# cs301_Group_12.net
KiCad netlist of a schematic drawn in Altium Designer
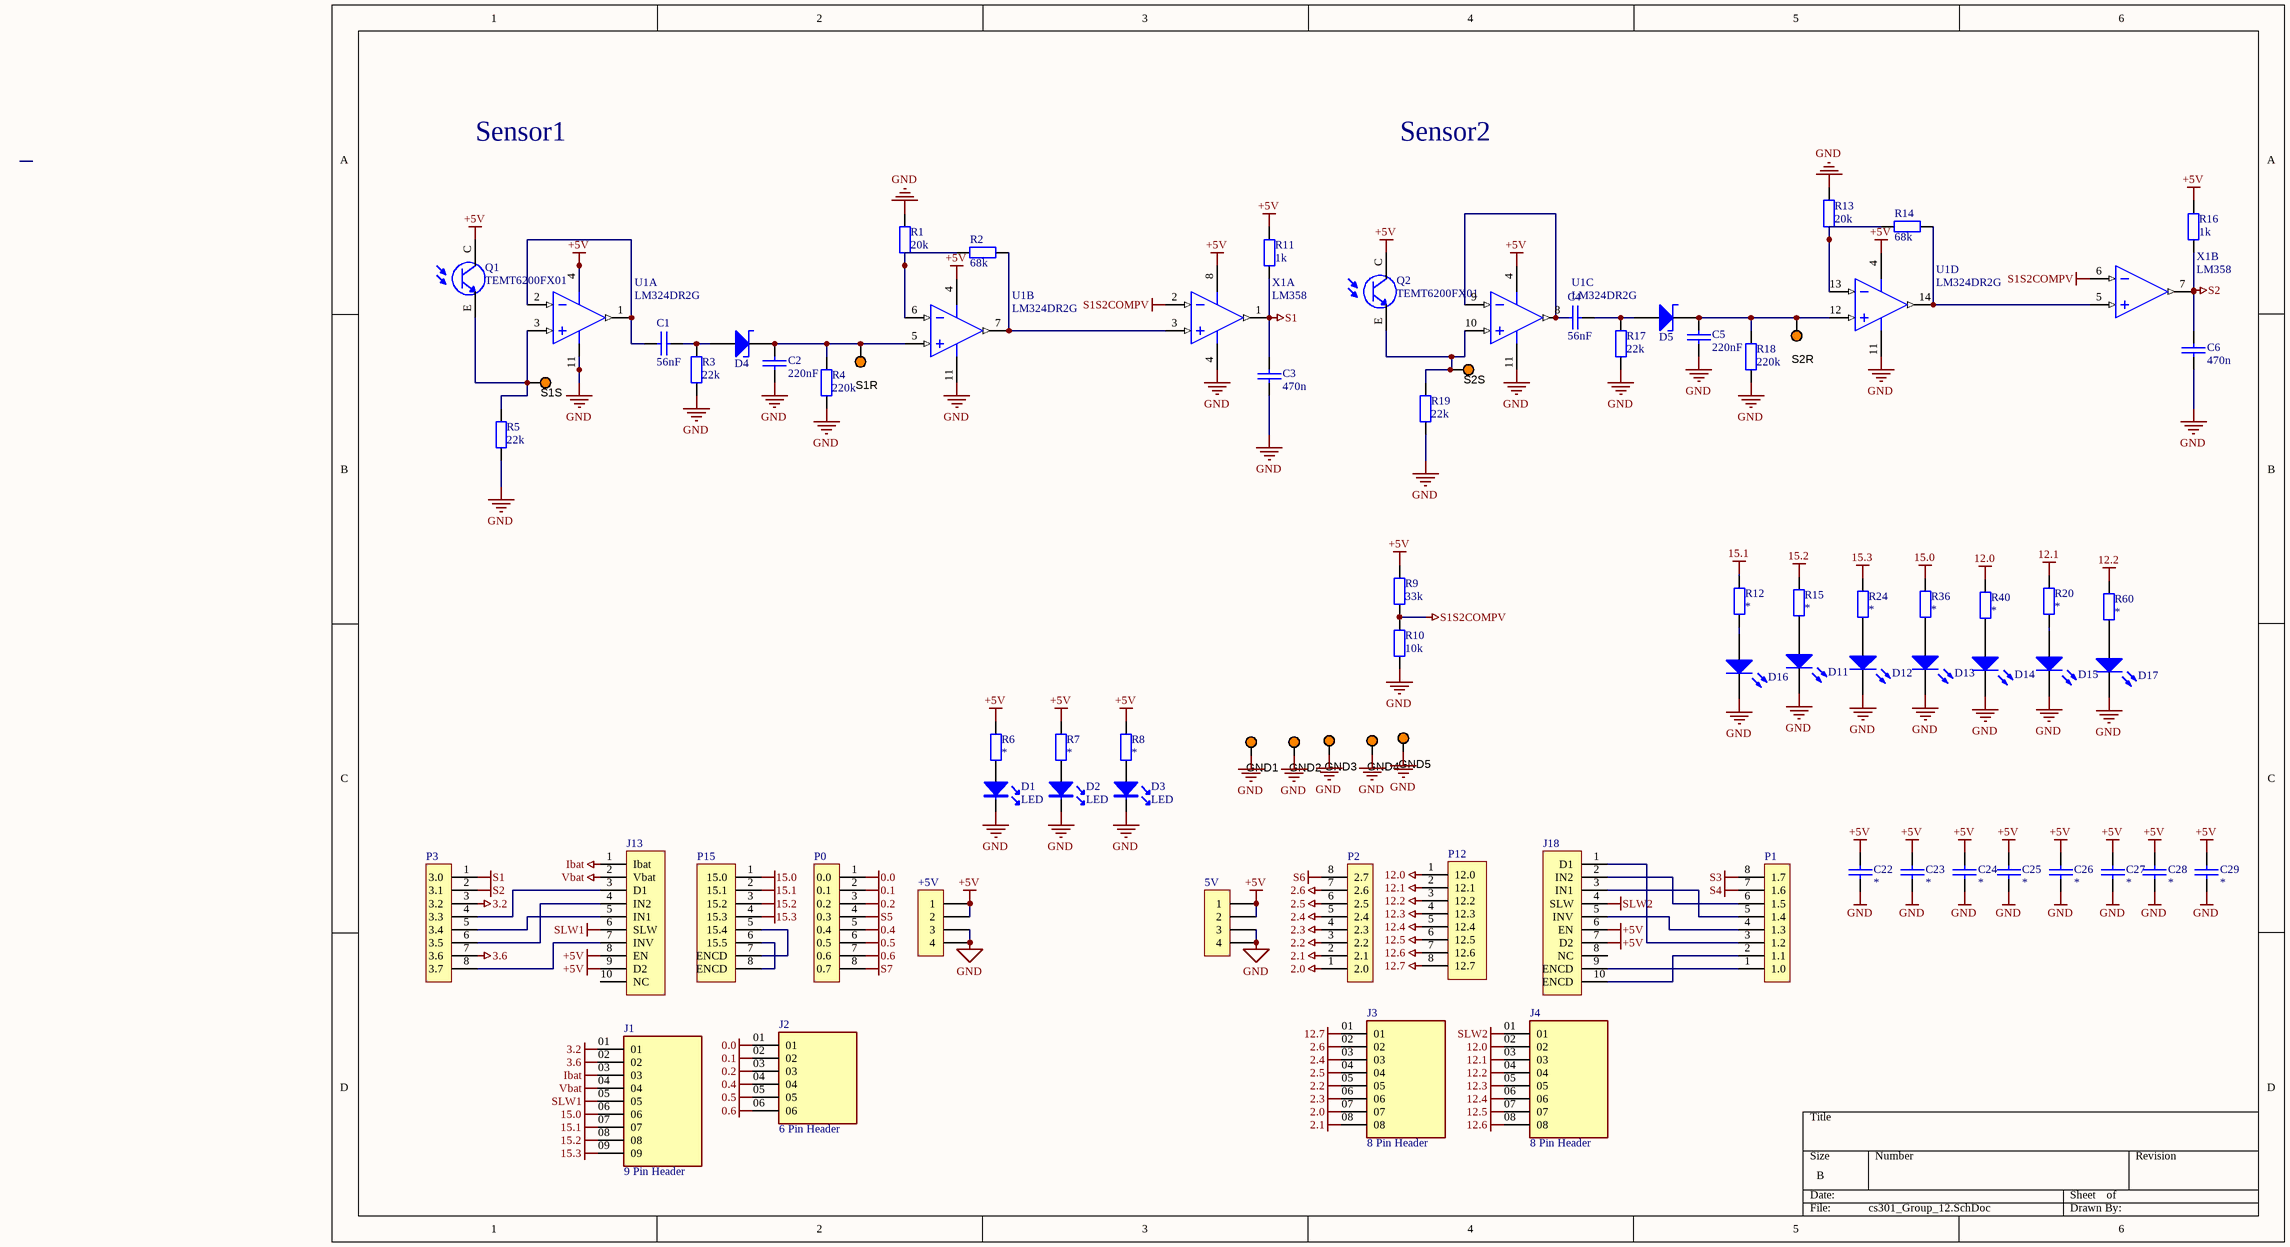
[diagram p0: cs301_Group_12.SchDoc]

(export (version "E")
  (design (tool "Eeschema 10.0.6"))
  (components
    (comp (ref "+5V")
      (value "5V")
      (footprint "IDC4")
      (description "Connector")
      (libsource (lib "Miscellaneous Devices") (part "CON4"))
    )
    (comp (ref "5V")
      (value "5V")
      (footprint "IDC4")
      (description "Connector")
      (libsource (lib "Miscellaneous Devices") (part "CON4"))
    )
    (comp (ref "C1")
      (value "56nF")
      (footprint "0805 CAP")
      (description "SMT ceramic capacitor 0805 size")
      (libsource (lib "EE209_Library") (part "CerCap_SMT_0805"))
    )
    (comp (ref "C2")
      (value "220nF")
      (footprint "0805 CAP")
      (description "SMT ceramic capacitor 0805 size")
      (libsource (lib "EE209_Library") (part "CerCap_SMT_0805"))
    )
    (comp (ref "C3")
      (value "470n")
      (footprint "0805 CAP")
      (description "SMT ceramic capacitor 0805 size")
      (libsource (lib "EE209_Library") (part "CerCap_SMT_0805"))
    )
    (comp (ref "C4")
      (value "56nF")
      (footprint "0805 CAP")
      (description "SMT ceramic capacitor 0805 size")
      (libsource (lib "EE209_Library") (part "CerCap_SMT_0805"))
    )
    (comp (ref "C5")
      (value "220nF")
      (footprint "0805 CAP")
      (description "SMT ceramic capacitor 0805 size")
      (libsource (lib "EE209_Library") (part "CerCap_SMT_0805"))
    )
    (comp (ref "C6")
      (value "470n")
      (footprint "0805 CAP")
      (description "SMT ceramic capacitor 0805 size")
      (libsource (lib "EE209_Library") (part "CerCap_SMT_0805"))
    )
    (comp (ref "C22")
      (value "*")
      (footprint "0805 CAP")
      (description "SMT ceramic capacitor 0805 size")
      (libsource (lib "EE209_Library") (part "CerCap_SMT_0805"))
    )
    (comp (ref "C23")
      (value "*")
      (footprint "0805 CAP")
      (description "SMT ceramic capacitor 0805 size")
      (libsource (lib "EE209_Library") (part "CerCap_SMT_0805"))
    )
    (comp (ref "C24")
      (value "*")
      (footprint "0805 CAP")
      (description "SMT ceramic capacitor 0805 size")
      (libsource (lib "EE209_Library") (part "CerCap_SMT_0805"))
    )
    (comp (ref "C25")
      (value "*")
      (footprint "0805 CAP")
      (description "SMT ceramic capacitor 0805 size")
      (libsource (lib "EE209_Library") (part "CerCap_SMT_0805"))
    )
    (comp (ref "C26")
      (value "*")
      (footprint "0805 CAP")
      (description "SMT ceramic capacitor 0805 size")
      (libsource (lib "EE209_Library") (part "CerCap_SMT_0805"))
    )
    (comp (ref "C27")
      (value "*")
      (footprint "0805 CAP")
      (description "SMT ceramic capacitor 0805 size")
      (libsource (lib "EE209_Library") (part "CerCap_SMT_0805"))
    )
    (comp (ref "C28")
      (value "*")
      (footprint "0805 CAP")
      (description "SMT ceramic capacitor 0805 size")
      (libsource (lib "EE209_Library") (part "CerCap_SMT_0805"))
    )
    (comp (ref "C29")
      (value "*")
      (footprint "0805 CAP")
      (description "SMT ceramic capacitor 0805 size")
      (libsource (lib "EE209_Library") (part "CerCap_SMT_0805"))
    )
    (comp (ref "D1") (value "LED") (footprint "LED0.1/5MM") (libsource (lib "COMSYS301_2013") (part "LED")))
    (comp (ref "D2") (value "LED") (footprint "LED0.1/5MM") (libsource (lib "COMSYS301_2013") (part "LED")))
    (comp (ref "D3") (value "LED") (footprint "LED0.1/5MM") (libsource (lib "COMSYS301_2013") (part "LED")))
    (comp (ref "D4")
      (value "BZT52H-B4V7")
      (footprint "SOD123")
      (description "SMT zener diode with SOD123 package")
      (fields
        (field (name "MANUFACTURER") "Nexperia USA Inc.")
        (field (name "MANUFACTURER PART NUMBER") "BZT52H-B4V7,115")
      )
      (libsource (lib "EE209_Library") (part "Zener_SMT_SOD123"))
    )
    (comp (ref "D5")
      (value "BZT52H-B4V7")
      (footprint "SOD123")
      (description "SMT zener diode with SOD123 package")
      (fields
        (field (name "MANUFACTURER") "Nexperia USA Inc.")
        (field (name "MANUFACTURER PART NUMBER") "BZT52H-B4V7,115")
      )
      (libsource (lib "EE209_Library") (part "Zener_SMT_SOD123"))
    )
    (comp (ref "D11")
      (value "LTST-C170KGKT")
      (footprint "0805 LED")
      (description "SMT LED 0805 size")
      (fields (field (name "MANUFACTURER") "Lite-On Inc."))
      (libsource (lib "EE209_Library") (part "LED_SMT_0805"))
    )
    (comp (ref "D12")
      (value "LTST-C170KGKT")
      (footprint "0805 LED")
      (description "SMT LED 0805 size")
      (fields (field (name "MANUFACTURER") "Lite-On Inc."))
      (libsource (lib "EE209_Library") (part "LED_SMT_0805"))
    )
    (comp (ref "D13")
      (value "LTST-C170KGKT")
      (footprint "0805 LED")
      (description "SMT LED 0805 size")
      (fields (field (name "MANUFACTURER") "Lite-On Inc."))
      (libsource (lib "EE209_Library") (part "LED_SMT_0805"))
    )
    (comp (ref "D14")
      (value "LTST-C170KGKT")
      (footprint "0805 LED")
      (description "SMT LED 0805 size")
      (fields (field (name "MANUFACTURER") "Lite-On Inc."))
      (libsource (lib "EE209_Library") (part "LED_SMT_0805"))
    )
    (comp (ref "D15")
      (value "LTST-C170KGKT")
      (footprint "0805 LED")
      (description "SMT LED 0805 size")
      (fields (field (name "MANUFACTURER") "Lite-On Inc."))
      (libsource (lib "EE209_Library") (part "LED_SMT_0805"))
    )
    (comp (ref "D16")
      (value "LTST-C170KGKT")
      (footprint "0805 LED")
      (description "SMT LED 0805 size")
      (fields (field (name "MANUFACTURER") "Lite-On Inc."))
      (libsource (lib "EE209_Library") (part "LED_SMT_0805"))
    )
    (comp (ref "D17")
      (value "LTST-C170KGKT")
      (footprint "0805 LED")
      (description "SMT LED 0805 size")
      (fields (field (name "MANUFACTURER") "Lite-On Inc."))
      (libsource (lib "EE209_Library") (part "LED_SMT_0805"))
    )
    (comp (ref "GND1")
      (value "5003")
      (footprint "TP_TH")
      (description "Test Point, Orange, 1-Pin THD, RoHS")
      (libsource (lib "EE209_Library") (part "TestPoint"))
    )
    (comp (ref "GND2")
      (value "5003")
      (footprint "TP_TH")
      (description "Test Point, Orange, 1-Pin THD, RoHS")
      (libsource (lib "EE209_Library") (part "TestPoint"))
    )
    (comp (ref "GND3")
      (value "5003")
      (footprint "TP_TH")
      (description "Test Point, Orange, 1-Pin THD, RoHS")
      (libsource (lib "EE209_Library") (part "TestPoint"))
    )
    (comp (ref "GND4")
      (value "5003")
      (footprint "TP_TH")
      (description "Test Point, Orange, 1-Pin THD, RoHS")
      (libsource (lib "EE209_Library") (part "TestPoint"))
    )
    (comp (ref "GND5")
      (value "5003")
      (footprint "TP_TH")
      (description "Test Point, Orange, 1-Pin THD, RoHS")
      (libsource (lib "EE209_Library") (part "TestPoint"))
    )
    (comp (ref "J1")
      (value "9 Pin Header")
      (footprint "SAMTEC_MTSW-109-22-G-S-440")
      (fields (field (name "MP") "MTSW-109-22-G-S-440"))
      (libsource (lib "MTSW-109-22-G-S-440") (part "MTSW-109-22-G-S-440"))
    )
    (comp (ref "J2")
      (value "6 Pin Header")
      (footprint "SAMTEC_TSW-106-07-H-S")
      (description "Connector Header Through Hole 6 position 0.100 (2.54mm)")
      (fields (field (name "MP") "TSW-106-07-H-S") (field (name "MF") "Samtec"))
      (libsource (lib "TSW-106-07-H-S") (part "TSW-106-07-H-S"))
    )
    (comp (ref "J3")
      (value "8 Pin Header")
      (footprint "SAMTEC_TSW-108-05-F-S")
      (fields (field (name "MP") "TSW-108-05-F-S"))
      (libsource (lib "TSW-108-05-F-S") (part "TSW-108-05-F-S"))
    )
    (comp (ref "J4")
      (value "8 Pin Header")
      (footprint "SAMTEC_TSW-108-05-F-S")
      (fields (field (name "MP") "TSW-108-05-F-S"))
      (libsource (lib "TSW-108-05-F-S") (part "TSW-108-05-F-S"))
    )
    (comp (ref "J13")
      (value "CON10")
      (footprint "idc10")
      (description "Connector")
      (libsource (lib "") (part "CON10_1"))
    )
    (comp (ref "J18")
      (value "CON10")
      (footprint "IDC10")
      (description "Connector")
      (libsource (lib "Miscellaneous Devices") (part "CON10"))
    )
    (comp (ref "P0")
      (value "P0")
      (footprint "idc8")
      (description "Connector")
      (libsource (lib "Miscellaneous Devices") (part "CON8"))
    )
    (comp (ref "P1")
      (value "P1")
      (footprint "idc8")
      (description "Connector")
      (libsource (lib "") (part "CON8_1"))
    )
    (comp (ref "P2")
      (value "P2")
      (footprint "idc8")
      (description "Connector")
      (libsource (lib "") (part "CON8_2"))
    )
    (comp (ref "P3")
      (value "P3")
      (footprint "idc8")
      (description "Connector")
      (libsource (lib "Miscellaneous Devices") (part "CON8"))
    )
    (comp (ref "P12")
      (value "P12")
      (footprint "idc8")
      (description "Connector")
      (libsource (lib "Miscellaneous Devices") (part "CON8_1"))
    )
    (comp (ref "P15")
      (value "P15")
      (footprint "idc8")
      (description "Connector")
      (libsource (lib "") (part "CON8_1_1"))
    )
    (comp (ref "Q1")
      (value "TEMT6200FX01")
      (footprint "XDCR_TEMT6200FX01")
      (description "Phototransistors 550nm Top View 0805 (2012 Metric)")
      (fields (field (name "MF") "Vishay Semiconductor"))
      (libsource (lib "TEMT6200FX01") (part "TEMT6200FX01"))
    )
    (comp (ref "Q2")
      (value "TEMT6200FX01")
      (footprint "XDCR_TEMT6200FX01")
      (description "Phototransistors 550nm Top View 0805 (2012 Metric)")
      (fields (field (name "MF") "Vishay Semiconductor"))
      (libsource (lib "TEMT6200FX01") (part "TEMT6200FX01"))
    )
    (comp (ref "R1")
      (value "20k")
      (footprint "0805 RES")
      (description "0805 resistor")
      (fields (field (name "PUBLISHER") "Altium Limited"))
      (libsource (lib "EE209_Library") (part "Res_SMT_0805"))
    )
    (comp (ref "R2")
      (value "68k")
      (footprint "0805 RES")
      (description "0805 resistor")
      (fields (field (name "PUBLISHER") "Altium Limited"))
      (libsource (lib "") (part "Res_SMT_0805_2"))
    )
    (comp (ref "R3")
      (value "22k")
      (footprint "0805 RES")
      (description "0805 resistor")
      (fields (field (name "PUBLISHER") "Altium Limited"))
      (libsource (lib "EE209_Library") (part "Res_SMT_0805"))
    )
    (comp (ref "R4")
      (value "220k")
      (footprint "0805 RES")
      (description "0805 resistor")
      (fields (field (name "PUBLISHER") "Altium Limited"))
      (libsource (lib "EE209_Library") (part "Res_SMT_0805"))
    )
    (comp (ref "R5")
      (value "22k")
      (footprint "0805 RES")
      (description "0805 resistor")
      (fields (field (name "PUBLISHER") "Altium Limited"))
      (libsource (lib "EE209_Library") (part "Res_SMT_0805"))
    )
    (comp (ref "R6")
      (value "*")
      (footprint "0805 RES")
      (description "0805 resistor")
      (fields (field (name "PUBLISHER") "Altium Limited"))
      (libsource (lib "EE209_Library") (part "Res_SMT_0805"))
    )
    (comp (ref "R7")
      (value "*")
      (footprint "0805 RES")
      (description "0805 resistor")
      (fields (field (name "PUBLISHER") "Altium Limited"))
      (libsource (lib "EE209_Library") (part "Res_SMT_0805"))
    )
    (comp (ref "R8")
      (value "*")
      (footprint "0805 RES")
      (description "0805 resistor")
      (fields (field (name "PUBLISHER") "Altium Limited"))
      (libsource (lib "EE209_Library") (part "Res_SMT_0805"))
    )
    (comp (ref "R9")
      (value "33k")
      (footprint "0805 RES")
      (description "0805 resistor")
      (fields (field (name "PUBLISHER") "Altium Limited"))
      (libsource (lib "") (part "Res_SMT_0805_1"))
    )
    (comp (ref "R10")
      (value "10k")
      (footprint "0805 RES")
      (description "0805 resistor")
      (fields (field (name "PUBLISHER") "Altium Limited"))
      (libsource (lib "") (part "Res_SMT_0805_1"))
    )
    (comp (ref "R11")
      (value "1k")
      (footprint "0805 RES")
      (description "0805 resistor")
      (fields (field (name "PUBLISHER") "Altium Limited"))
      (libsource (lib "") (part "Res_SMT_0805_1"))
    )
    (comp (ref "R12")
      (value "*")
      (footprint "0805 RES")
      (description "0805 resistor")
      (fields (field (name "PUBLISHER") "Altium Limited"))
      (libsource (lib "EE209_Library") (part "Res_SMT_0805"))
    )
    (comp (ref "R13")
      (value "20k")
      (footprint "0805 RES")
      (description "0805 resistor")
      (fields (field (name "PUBLISHER") "Altium Limited"))
      (libsource (lib "EE209_Library") (part "Res_SMT_0805"))
    )
    (comp (ref "R14")
      (value "68k")
      (footprint "0805 RES")
      (description "0805 resistor")
      (fields (field (name "PUBLISHER") "Altium Limited"))
      (libsource (lib "") (part "Res_SMT_0805_2"))
    )
    (comp (ref "R15")
      (value "*")
      (footprint "0805 RES")
      (description "0805 resistor")
      (fields (field (name "PUBLISHER") "Altium Limited"))
      (libsource (lib "EE209_Library") (part "Res_SMT_0805"))
    )
    (comp (ref "R16")
      (value "1k")
      (footprint "0805 RES")
      (description "0805 resistor")
      (fields (field (name "PUBLISHER") "Altium Limited"))
      (libsource (lib "") (part "Res_SMT_0805_1"))
    )
    (comp (ref "R17")
      (value "22k")
      (footprint "0805 RES")
      (description "0805 resistor")
      (fields (field (name "PUBLISHER") "Altium Limited"))
      (libsource (lib "EE209_Library") (part "Res_SMT_0805"))
    )
    (comp (ref "R18")
      (value "220k")
      (footprint "0805 RES")
      (description "0805 resistor")
      (fields (field (name "PUBLISHER") "Altium Limited"))
      (libsource (lib "EE209_Library") (part "Res_SMT_0805"))
    )
    (comp (ref "R19")
      (value "22k")
      (footprint "0805 RES")
      (description "0805 resistor")
      (fields (field (name "PUBLISHER") "Altium Limited"))
      (libsource (lib "EE209_Library") (part "Res_SMT_0805"))
    )
    (comp (ref "R20")
      (value "*")
      (footprint "0805 RES")
      (description "0805 resistor")
      (fields (field (name "PUBLISHER") "Altium Limited"))
      (libsource (lib "EE209_Library") (part "Res_SMT_0805"))
    )
    (comp (ref "R24")
      (value "*")
      (footprint "0805 RES")
      (description "0805 resistor")
      (fields (field (name "PUBLISHER") "Altium Limited"))
      (libsource (lib "EE209_Library") (part "Res_SMT_0805"))
    )
    (comp (ref "R36")
      (value "*")
      (footprint "0805 RES")
      (description "0805 resistor")
      (fields (field (name "PUBLISHER") "Altium Limited"))
      (libsource (lib "EE209_Library") (part "Res_SMT_0805"))
    )
    (comp (ref "R40")
      (value "*")
      (footprint "0805 RES")
      (description "0805 resistor")
      (fields (field (name "PUBLISHER") "Altium Limited"))
      (libsource (lib "EE209_Library") (part "Res_SMT_0805"))
    )
    (comp (ref "R60")
      (value "*")
      (footprint "0805 RES")
      (description "0805 resistor")
      (fields (field (name "PUBLISHER") "Altium Limited"))
      (libsource (lib "EE209_Library") (part "Res_SMT_0805"))
    )
    (comp (ref "S1R")
      (value "5003")
      (footprint "TP_TH")
      (description "Test Point, Orange, 1-Pin THD, RoHS")
      (libsource (lib "EE209_Library") (part "TestPoint"))
    )
    (comp (ref "S1S")
      (value "5003")
      (footprint "TP_TH")
      (description "Test Point, Orange, 1-Pin THD, RoHS")
      (libsource (lib "EE209_Library") (part "TestPoint"))
    )
    (comp (ref "S2R")
      (value "5003")
      (footprint "TP_TH")
      (description "Test Point, Orange, 1-Pin THD, RoHS")
      (libsource (lib "EE209_Library") (part "TestPoint"))
    )
    (comp (ref "S2S")
      (value "5003")
      (footprint "TP_TH")
      (description "Test Point, Orange, 1-Pin THD, RoHS")
      (libsource (lib "EE209_Library") (part "TestPoint"))
    )
    (comp (ref "U1")
      (value "LM324DR2G")
      (footprint "SOIC-14")
      (fields (field (name "MANUFACTURER") "On Semiconductor"))
      (libsource (lib "EE209_Library") (part "LM324DR_SMT_SOIC16"))
    )
    (comp (ref "X1")
      (value "LM358")
      (footprint "SO - 8")
      (description "IC OPAMP 8SOIC")
      (libsource (lib "EE209_Library") (part "LM358_SMT_SOIC8"))
    )
  )
  (nets
    (net (code "1") (name "+5V") (class "Default")
      (node (ref "+5V") (pin "1") (pinfunction "1_1") (pintype "passive"))
      (node (ref "+5V") (pin "2") (pinfunction "2_2") (pintype "passive"))
      (node (ref "5V") (pin "1") (pinfunction "1_1") (pintype "passive"))
      (node (ref "5V") (pin "2") (pinfunction "2_2") (pintype "passive"))
      (node (ref "C22") (pin "1") (pinfunction "1_1") (pintype "passive"))
      (node (ref "C23") (pin "1") (pinfunction "1_1") (pintype "passive"))
      (node (ref "C24") (pin "1") (pinfunction "1_1") (pintype "passive"))
      (node (ref "C25") (pin "1") (pinfunction "1_1") (pintype "passive"))
      (node (ref "C26") (pin "1") (pinfunction "1_1") (pintype "passive"))
      (node (ref "C27") (pin "1") (pinfunction "1_1") (pintype "passive"))
      (node (ref "C28") (pin "1") (pinfunction "1_1") (pintype "passive"))
      (node (ref "C29") (pin "1") (pinfunction "1_1") (pintype "passive"))
      (node (ref "J13") (pin "8") (pinfunction "EN_8") (pintype "passive"))
      (node (ref "J13") (pin "9") (pinfunction "D2_9") (pintype "passive"))
      (node (ref "J18") (pin "6") (pinfunction "EN_6") (pintype "passive"))
      (node (ref "J18") (pin "7") (pinfunction "D2_7") (pintype "passive"))
      (node (ref "Q1") (pin "C") (pinfunction "C_C") (pintype "passive"))
      (node (ref "Q2") (pin "C") (pinfunction "C_C") (pintype "passive"))
      (node (ref "R11") (pin "1") (pinfunction "1_1") (pintype "passive"))
      (node (ref "R16") (pin "1") (pinfunction "1_1") (pintype "passive"))
      (node (ref "R6") (pin "2") (pinfunction "2_2") (pintype "passive"))
      (node (ref "R7") (pin "2") (pinfunction "2_2") (pintype "passive"))
      (node (ref "R8") (pin "2") (pinfunction "2_2") (pintype "passive"))
      (node (ref "R9") (pin "1") (pinfunction "1_1") (pintype "passive"))
      (node (ref "U1") (pin "4") (pinfunction "VCC_4") (pintype "power_in"))
      (node (ref "X1") (pin "8") (pinfunction "VDD_8") (pintype "power_in"))
    )
    (net (code "2") (name "0.0") (class "Default")
      (node (ref "J2") (pin "01") (pinfunction "01_01") (pintype "passive"))
      (node (ref "P0") (pin "1") (pinfunction "3.0_1") (pintype "passive"))
    )
    (net (code "3") (name "0.1") (class "Default")
      (node (ref "J2") (pin "02") (pinfunction "02_02") (pintype "passive"))
      (node (ref "P0") (pin "2") (pinfunction "3.1_2") (pintype "passive"))
    )
    (net (code "4") (name "0.2") (class "Default")
      (node (ref "J2") (pin "03") (pinfunction "03_03") (pintype "passive"))
      (node (ref "P0") (pin "3") (pinfunction "3.2_3") (pintype "passive"))
    )
    (net (code "5") (name "0.4") (class "Default")
      (node (ref "J2") (pin "04") (pinfunction "04_04") (pintype "passive"))
      (node (ref "P0") (pin "5") (pinfunction "3.4_5") (pintype "passive"))
    )
    (net (code "6") (name "0.5") (class "Default")
      (node (ref "J2") (pin "05") (pinfunction "05_05") (pintype "passive"))
      (node (ref "P0") (pin "6") (pinfunction "3.5_6") (pintype "passive"))
    )
    (net (code "7") (name "0.6") (class "Default")
      (node (ref "J2") (pin "06") (pinfunction "06_06") (pintype "passive"))
      (node (ref "P0") (pin "7") (pinfunction "3.6_7") (pintype "passive"))
    )
    (net (code "8") (name "2.0") (class "Default")
      (node (ref "J3") (pin "07") (pinfunction "07_07") (pintype "passive"))
      (node (ref "P2") (pin "1") (pinfunction "2.0_1") (pintype "passive"))
    )
    (net (code "9") (name "2.1") (class "Default")
      (node (ref "J3") (pin "08") (pinfunction "08_08") (pintype "passive"))
      (node (ref "P2") (pin "2") (pinfunction "2.1_2") (pintype "passive"))
    )
    (net (code "10") (name "2.2") (class "Default")
      (node (ref "J3") (pin "05") (pinfunction "05_05") (pintype "passive"))
      (node (ref "P2") (pin "3") (pinfunction "2.2_3") (pintype "passive"))
    )
    (net (code "11") (name "2.3") (class "Default")
      (node (ref "J3") (pin "06") (pinfunction "06_06") (pintype "passive"))
      (node (ref "P2") (pin "4") (pinfunction "2.3_4") (pintype "passive"))
    )
    (net (code "12") (name "2.4") (class "Default")
      (node (ref "J3") (pin "03") (pinfunction "03_03") (pintype "passive"))
      (node (ref "P2") (pin "5") (pinfunction "2.4_5") (pintype "passive"))
    )
    (net (code "13") (name "2.5") (class "Default")
      (node (ref "J3") (pin "04") (pinfunction "04_04") (pintype "passive"))
      (node (ref "P2") (pin "6") (pinfunction "2.5_6") (pintype "passive"))
    )
    (net (code "14") (name "2.6") (class "Default")
      (node (ref "J3") (pin "02") (pinfunction "02_02") (pintype "passive"))
      (node (ref "P2") (pin "7") (pinfunction "2.6_7") (pintype "passive"))
    )
    (net (code "15") (name "3.2") (class "Default")
      (node (ref "J1") (pin "01") (pinfunction "01_01") (pintype "passive"))
      (node (ref "P3") (pin "3") (pinfunction "3.2_3") (pintype "passive"))
    )
    (net (code "16") (name "3.6") (class "Default")
      (node (ref "J1") (pin "02") (pinfunction "02_02") (pintype "passive"))
      (node (ref "P3") (pin "7") (pinfunction "3.6_7") (pintype "passive"))
    )
    (net (code "17") (name "12.0") (class "Default")
      (node (ref "J4") (pin "02") (pinfunction "02_02") (pintype "passive"))
      (node (ref "P12") (pin "1") (pinfunction "12.0_1") (pintype "passive"))
      (node (ref "R40") (pin "2") (pinfunction "2_2") (pintype "passive"))
    )
    (net (code "18") (name "12.1") (class "Default")
      (node (ref "J4") (pin "03") (pinfunction "03_03") (pintype "passive"))
      (node (ref "P12") (pin "2") (pinfunction "12.1_2") (pintype "passive"))
      (node (ref "R20") (pin "2") (pinfunction "2_2") (pintype "passive"))
    )
    (net (code "19") (name "12.2") (class "Default")
      (node (ref "J4") (pin "04") (pinfunction "04_04") (pintype "passive"))
      (node (ref "P12") (pin "3") (pinfunction "12.2_3") (pintype "passive"))
      (node (ref "R60") (pin "2") (pinfunction "2_2") (pintype "passive"))
    )
    (net (code "20") (name "12.3") (class "Default")
      (node (ref "J4") (pin "05") (pinfunction "05_05") (pintype "passive"))
      (node (ref "P12") (pin "4") (pinfunction "12.3_4") (pintype "passive"))
    )
    (net (code "21") (name "12.4") (class "Default")
      (node (ref "J4") (pin "06") (pinfunction "06_06") (pintype "passive"))
      (node (ref "P12") (pin "5") (pinfunction "12.4_5") (pintype "passive"))
    )
    (net (code "22") (name "12.5") (class "Default")
      (node (ref "J4") (pin "07") (pinfunction "07_07") (pintype "passive"))
      (node (ref "P12") (pin "6") (pinfunction "12.5_6") (pintype "passive"))
    )
    (net (code "23") (name "12.6") (class "Default")
      (node (ref "J4") (pin "08") (pinfunction "08_08") (pintype "passive"))
      (node (ref "P12") (pin "7") (pinfunction "12.6_7") (pintype "passive"))
    )
    (net (code "24") (name "12.7") (class "Default")
      (node (ref "J3") (pin "01") (pinfunction "01_01") (pintype "passive"))
      (node (ref "P12") (pin "8") (pinfunction "12.7_8") (pintype "passive"))
    )
    (net (code "25") (name "15.0") (class "Default")
      (node (ref "J1") (pin "06") (pinfunction "06_06") (pintype "passive"))
      (node (ref "P15") (pin "1") (pinfunction "15.0_1") (pintype "passive"))
      (node (ref "R36") (pin "2") (pinfunction "2_2") (pintype "passive"))
    )
    (net (code "26") (name "15.1") (class "Default")
      (node (ref "J1") (pin "07") (pinfunction "07_07") (pintype "passive"))
      (node (ref "P15") (pin "2") (pinfunction "15.1_2") (pintype "passive"))
      (node (ref "R12") (pin "2") (pinfunction "2_2") (pintype "passive"))
    )
    (net (code "27") (name "15.2") (class "Default")
      (node (ref "J1") (pin "08") (pinfunction "08_08") (pintype "passive"))
      (node (ref "P15") (pin "3") (pinfunction "15.2_3") (pintype "passive"))
      (node (ref "R15") (pin "2") (pinfunction "2_2") (pintype "passive"))
    )
    (net (code "28") (name "15.3") (class "Default")
      (node (ref "J1") (pin "09") (pinfunction "09_09") (pintype "passive"))
      (node (ref "P15") (pin "4") (pinfunction "15.3_4") (pintype "passive"))
      (node (ref "R24") (pin "2") (pinfunction "2_2") (pintype "passive"))
    )
    (net (code "29") (name "GND") (class "Default")
      (node (ref "+5V") (pin "3") (pinfunction "3_3") (pintype "passive"))
      (node (ref "+5V") (pin "4") (pinfunction "4_4") (pintype "passive"))
      (node (ref "5V") (pin "3") (pinfunction "3_3") (pintype "passive"))
      (node (ref "5V") (pin "4") (pinfunction "4_4") (pintype "passive"))
      (node (ref "C2") (pin "2") (pinfunction "2_2") (pintype "passive"))
      (node (ref "C22") (pin "2") (pinfunction "2_2") (pintype "passive"))
      (node (ref "C23") (pin "2") (pinfunction "2_2") (pintype "passive"))
      (node (ref "C24") (pin "2") (pinfunction "2_2") (pintype "passive"))
      (node (ref "C25") (pin "2") (pinfunction "2_2") (pintype "passive"))
      (node (ref "C26") (pin "2") (pinfunction "2_2") (pintype "passive"))
      (node (ref "C27") (pin "2") (pinfunction "2_2") (pintype "passive"))
      (node (ref "C28") (pin "2") (pinfunction "2_2") (pintype "passive"))
      (node (ref "C29") (pin "2") (pinfunction "2_2") (pintype "passive"))
      (node (ref "C3") (pin "2") (pinfunction "2_2") (pintype "passive"))
      (node (ref "C5") (pin "2") (pinfunction "2_2") (pintype "passive"))
      (node (ref "C6") (pin "2") (pinfunction "2_2") (pintype "passive"))
      (node (ref "D1") (pin "K") (pinfunction "2_K") (pintype "passive"))
      (node (ref "D11") (pin "2") (pinfunction "K_2") (pintype "passive"))
      (node (ref "D12") (pin "2") (pinfunction "K_2") (pintype "passive"))
      (node (ref "D13") (pin "2") (pinfunction "K_2") (pintype "passive"))
      (node (ref "D14") (pin "2") (pinfunction "K_2") (pintype "passive"))
      (node (ref "D15") (pin "2") (pinfunction "K_2") (pintype "passive"))
      (node (ref "D16") (pin "2") (pinfunction "K_2") (pintype "passive"))
      (node (ref "D17") (pin "2") (pinfunction "K_2") (pintype "passive"))
      (node (ref "D2") (pin "K") (pinfunction "2_K") (pintype "passive"))
      (node (ref "D3") (pin "K") (pinfunction "2_K") (pintype "passive"))
      (node (ref "R1") (pin "2") (pinfunction "2_2") (pintype "passive"))
      (node (ref "R10") (pin "2") (pinfunction "2_2") (pintype "passive"))
      (node (ref "R13") (pin "2") (pinfunction "2_2") (pintype "passive"))
      (node (ref "R17") (pin "1") (pinfunction "1_1") (pintype "passive"))
      (node (ref "R18") (pin "1") (pinfunction "1_1") (pintype "passive"))
      (node (ref "R19") (pin "1") (pinfunction "1_1") (pintype "passive"))
      (node (ref "R3") (pin "1") (pinfunction "1_1") (pintype "passive"))
      (node (ref "R4") (pin "1") (pinfunction "1_1") (pintype "passive"))
      (node (ref "R5") (pin "1") (pinfunction "1_1") (pintype "passive"))
      (node (ref "U1") (pin "11") (pinfunction "VEE/GND_11") (pintype "power_in"))
      (node (ref "X1") (pin "4") (pinfunction "VSS_4") (pintype "power_in"))
    )
    (net (code "30") (name "Ibat") (class "Default")
      (node (ref "J1") (pin "03") (pinfunction "03_03") (pintype "passive"))
      (node (ref "J13") (pin "1") (pinfunction "Ibat_1") (pintype "passive"))
    )
    (net (code "31") (name "Net-(D1-1)") (class "Default")
      (node (ref "D1") (pin "A") (pinfunction "1_A") (pintype "passive"))
      (node (ref "R6") (pin "1") (pinfunction "1_1") (pintype "passive"))
    )
    (net (code "32") (name "Net-(D2-1)") (class "Default")
      (node (ref "D2") (pin "A") (pinfunction "1_A") (pintype "passive"))
      (node (ref "R7") (pin "1") (pinfunction "1_1") (pintype "passive"))
    )
    (net (code "33") (name "Net-(D3-1)") (class "Default")
      (node (ref "D3") (pin "A") (pinfunction "1_A") (pintype "passive"))
      (node (ref "R8") (pin "1") (pinfunction "1_1") (pintype "passive"))
    )
    (net (code "34") (name "Net-(D4-A)") (class "Default")
      (node (ref "C1") (pin "2") (pinfunction "2_2") (pintype "passive"))
      (node (ref "D4") (pin "1") (pinfunction "A_1") (pintype "passive"))
      (node (ref "R3") (pin "2") (pinfunction "2_2") (pintype "passive"))
    )
    (net (code "35") (name "Net-(D4-K)") (class "Default")
      (node (ref "C2") (pin "1") (pinfunction "1_1") (pintype "passive"))
      (node (ref "D4") (pin "2") (pinfunction "K_2") (pintype "passive"))
      (node (ref "R4") (pin "2") (pinfunction "2_2") (pintype "passive"))
      (node (ref "S1R") (pin "1") (pinfunction "1_1") (pintype "passive"))
      (node (ref "U1") (pin "5") (pinfunction "IN2+_5") (pintype "input"))
    )
    (net (code "36") (name "Net-(D5-A)") (class "Default")
      (node (ref "C4") (pin "2") (pinfunction "2_2") (pintype "passive"))
      (node (ref "D5") (pin "1") (pinfunction "A_1") (pintype "passive"))
      (node (ref "R17") (pin "2") (pinfunction "2_2") (pintype "passive"))
    )
    (net (code "37") (name "Net-(D5-K)") (class "Default")
      (node (ref "C5") (pin "1") (pinfunction "1_1") (pintype "passive"))
      (node (ref "D5") (pin "2") (pinfunction "K_2") (pintype "passive"))
      (node (ref "R18") (pin "2") (pinfunction "2_2") (pintype "passive"))
      (node (ref "S2R") (pin "1") (pinfunction "1_1") (pintype "passive"))
      (node (ref "U1") (pin "12") (pinfunction "IN4+_12") (pintype "input"))
    )
    (net (code "38") (name "Net-(D11-A)") (class "Default")
      (node (ref "D11") (pin "1") (pinfunction "A_1") (pintype "passive"))
      (node (ref "R15") (pin "1") (pinfunction "1_1") (pintype "passive"))
    )
    (net (code "39") (name "Net-(D12-A)") (class "Default")
      (node (ref "D12") (pin "1") (pinfunction "A_1") (pintype "passive"))
      (node (ref "R24") (pin "1") (pinfunction "1_1") (pintype "passive"))
    )
    (net (code "40") (name "Net-(D13-A)") (class "Default")
      (node (ref "D13") (pin "1") (pinfunction "A_1") (pintype "passive"))
      (node (ref "R36") (pin "1") (pinfunction "1_1") (pintype "passive"))
    )
    (net (code "41") (name "Net-(D14-A)") (class "Default")
      (node (ref "D14") (pin "1") (pinfunction "A_1") (pintype "passive"))
      (node (ref "R40") (pin "1") (pinfunction "1_1") (pintype "passive"))
    )
    (net (code "42") (name "Net-(D15-A)") (class "Default")
      (node (ref "D15") (pin "1") (pinfunction "A_1") (pintype "passive"))
      (node (ref "R20") (pin "1") (pinfunction "1_1") (pintype "passive"))
    )
    (net (code "43") (name "Net-(D16-A)") (class "Default")
      (node (ref "D16") (pin "1") (pinfunction "A_1") (pintype "passive"))
      (node (ref "R12") (pin "1") (pinfunction "1_1") (pintype "passive"))
    )
    (net (code "44") (name "Net-(D17-A)") (class "Default")
      (node (ref "D17") (pin "1") (pinfunction "A_1") (pintype "passive"))
      (node (ref "R60") (pin "1") (pinfunction "1_1") (pintype "passive"))
    )
    (net (code "45") (name "Net-(J13-D1)") (class "Default")
      (node (ref "J13") (pin "3") (pinfunction "D1_3") (pintype "passive"))
      (node (ref "P3") (pin "4") (pinfunction "3.3_4") (pintype "passive"))
    )
    (net (code "46") (name "Net-(J13-IN1)") (class "Default")
      (node (ref "J13") (pin "5") (pinfunction "IN1_5") (pintype "passive"))
      (node (ref "P3") (pin "5") (pinfunction "3.4_5") (pintype "passive"))
    )
    (net (code "47") (name "Net-(J13-IN2)") (class "Default")
      (node (ref "J13") (pin "4") (pinfunction "IN2_4") (pintype "passive"))
      (node (ref "P3") (pin "6") (pinfunction "3.5_6") (pintype "passive"))
    )
    (net (code "48") (name "Net-(J13-INV)") (class "Default")
      (node (ref "J13") (pin "7") (pinfunction "INV_7") (pintype "passive"))
      (node (ref "P3") (pin "8") (pinfunction "3.7_8") (pintype "passive"))
    )
    (net (code "49") (name "Net-(J18-D1)") (class "Default")
      (node (ref "J18") (pin "1") (pinfunction "D1_1") (pintype "passive"))
      (node (ref "P1") (pin "3") (pinfunction "1.2_3") (pintype "passive"))
    )
    (net (code "50") (name "Net-(J18-IN1)") (class "Default")
      (node (ref "J18") (pin "3") (pinfunction "IN1_3") (pintype "passive"))
      (node (ref "P1") (pin "5") (pinfunction "1.4_5") (pintype "passive"))
    )
    (net (code "51") (name "Net-(J18-IN2)") (class "Default")
      (node (ref "J18") (pin "2") (pinfunction "IN2_2") (pintype "passive"))
      (node (ref "P1") (pin "6") (pinfunction "1.5_6") (pintype "passive"))
    )
    (net (code "52") (name "Net-(J18-INV)") (class "Default")
      (node (ref "J18") (pin "5") (pinfunction "INV_5") (pintype "passive"))
      (node (ref "P1") (pin "4") (pinfunction "1.3_4") (pintype "passive"))
    )
    (net (code "53") (name "Net-(P1-1.0)") (class "Default")
      (node (ref "J18") (pin "9") (pinfunction "ENCD_9") (pintype "passive"))
      (node (ref "P1") (pin "1") (pinfunction "1.0_1") (pintype "passive"))
    )
    (net (code "54") (name "Net-(P1-1.1)") (class "Default")
      (node (ref "J18") (pin "10") (pinfunction "ENCD_10") (pintype "passive"))
      (node (ref "P1") (pin "2") (pinfunction "1.1_2") (pintype "passive"))
    )
    (net (code "55") (name "Net-(P15-15.4)") (class "Default")
      (node (ref "P15") (pin "5") (pinfunction "15.4_5") (pintype "passive"))
      (node (ref "P15") (pin "7") (pinfunction "ENCD_7") (pintype "passive"))
    )
    (net (code "56") (name "Net-(P15-15.5)") (class "Default")
      (node (ref "P15") (pin "6") (pinfunction "15.5_6") (pintype "passive"))
      (node (ref "P15") (pin "8") (pinfunction "ENCD_8") (pintype "passive"))
    )
    (net (code "57") (name "Net-(U1A-IN1+)") (class "Default")
      (node (ref "Q1") (pin "E") (pinfunction "E_E") (pintype "passive"))
      (node (ref "R5") (pin "2") (pinfunction "2_2") (pintype "passive"))
      (node (ref "S1S") (pin "1") (pinfunction "1_1") (pintype "passive"))
      (node (ref "U1") (pin "3") (pinfunction "IN1+_3") (pintype "input"))
    )
    (net (code "58") (name "Net-(U1A-IN1-)") (class "Default")
      (node (ref "C1") (pin "1") (pinfunction "1_1") (pintype "passive"))
      (node (ref "U1") (pin "1") (pinfunction "OUT1_1") (pintype "output"))
      (node (ref "U1") (pin "2") (pinfunction "IN1-_2") (pintype "input"))
    )
    (net (code "59") (name "Net-(U1B-IN2-)") (class "Default")
      (node (ref "R1") (pin "1") (pinfunction "1_1") (pintype "passive"))
      (node (ref "R2") (pin "2") (pinfunction "2_2") (pintype "passive"))
      (node (ref "U1") (pin "6") (pinfunction "IN2-_6") (pintype "input"))
    )
    (net (code "60") (name "Net-(U1B-OUT2)") (class "Default")
      (node (ref "R2") (pin "1") (pinfunction "1_1") (pintype "passive"))
      (node (ref "U1") (pin "7") (pinfunction "OUT2_7") (pintype "output"))
      (node (ref "X1") (pin "3") (pinfunction "VINA+_3") (pintype "input"))
    )
    (net (code "61") (name "Net-(U1C-IN3+)") (class "Default")
      (node (ref "Q2") (pin "E") (pinfunction "E_E") (pintype "passive"))
      (node (ref "R19") (pin "2") (pinfunction "2_2") (pintype "passive"))
      (node (ref "S2S") (pin "1") (pinfunction "1_1") (pintype "passive"))
      (node (ref "U1") (pin "10") (pinfunction "IN3+_10") (pintype "input"))
    )
    (net (code "62") (name "Net-(U1C-IN3-)") (class "Default")
      (node (ref "C4") (pin "1") (pinfunction "1_1") (pintype "passive"))
      (node (ref "U1") (pin "8") (pinfunction "OUT3_8") (pintype "output"))
      (node (ref "U1") (pin "9") (pinfunction "IN3-_9") (pintype "input"))
    )
    (net (code "63") (name "Net-(U1D-IN4-)") (class "Default")
      (node (ref "R13") (pin "1") (pinfunction "1_1") (pintype "passive"))
      (node (ref "R14") (pin "2") (pinfunction "2_2") (pintype "passive"))
      (node (ref "U1") (pin "13") (pinfunction "IN4-_13") (pintype "input"))
    )
    (net (code "64") (name "Net-(U1D-OUT4)") (class "Default")
      (node (ref "R14") (pin "1") (pinfunction "1_1") (pintype "passive"))
      (node (ref "U1") (pin "14") (pinfunction "OUT4_14") (pintype "output"))
      (node (ref "X1") (pin "5") (pinfunction "VINA+_5") (pintype "input"))
    )
    (net (code "65") (name "S1") (class "Default")
      (node (ref "C3") (pin "1") (pinfunction "1_1") (pintype "passive"))
      (node (ref "P3") (pin "1") (pinfunction "3.0_1") (pintype "passive"))
      (node (ref "R11") (pin "2") (pinfunction "2_2") (pintype "passive"))
      (node (ref "X1") (pin "1") (pinfunction "VOUTA_1") (pintype "output"))
    )
    (net (code "66") (name "S1S2COMPV") (class "Default")
      (node (ref "R10") (pin "1") (pinfunction "1_1") (pintype "passive"))
      (node (ref "R9") (pin "2") (pinfunction "2_2") (pintype "passive"))
      (node (ref "X1") (pin "2") (pinfunction "VINA-_2") (pintype "input"))
      (node (ref "X1") (pin "6") (pinfunction "VINA-_6") (pintype "input"))
    )
    (net (code "67") (name "S2") (class "Default")
      (node (ref "C6") (pin "1") (pinfunction "1_1") (pintype "passive"))
      (node (ref "P3") (pin "2") (pinfunction "3.1_2") (pintype "passive"))
      (node (ref "R16") (pin "2") (pinfunction "2_2") (pintype "passive"))
      (node (ref "X1") (pin "7") (pinfunction "VOUTA_7") (pintype "output"))
    )
    (net (code "68") (name "S3") (class "Default")
      (node (ref "P1") (pin "8") (pinfunction "1.7_8") (pintype "passive"))
    )
    (net (code "69") (name "S4") (class "Default")
      (node (ref "P1") (pin "7") (pinfunction "1.6_7") (pintype "passive"))
    )
    (net (code "70") (name "S5") (class "Default")
      (node (ref "P0") (pin "4") (pinfunction "3.3_4") (pintype "passive"))
    )
    (net (code "71") (name "S6") (class "Default")
      (node (ref "P2") (pin "8") (pinfunction "2.7_8") (pintype "passive"))
    )
    (net (code "72") (name "S7") (class "Default")
      (node (ref "P0") (pin "8") (pinfunction "3.7_8") (pintype "passive"))
    )
    (net (code "73") (name "SLW1") (class "Default")
      (node (ref "J1") (pin "05") (pinfunction "05_05") (pintype "passive"))
      (node (ref "J13") (pin "6") (pinfunction "SLW_6") (pintype "passive"))
    )
    (net (code "74") (name "SLW2") (class "Default")
      (node (ref "J18") (pin "4") (pinfunction "SLW_4") (pintype "passive"))
      (node (ref "J4") (pin "01") (pinfunction "01_01") (pintype "passive"))
    )
    (net (code "75") (name "Vbat") (class "Default")
      (node (ref "J1") (pin "04") (pinfunction "04_04") (pintype "passive"))
      (node (ref "J13") (pin "2") (pinfunction "Vbat_2") (pintype "passive"))
    )
    (net (code "76") (name "unconnected-(GND1-Pad1)") (class "Default")
      (node (ref "GND1") (pin "1") (pinfunction "1_1") (pintype "passive"))
    )
    (net (code "77") (name "unconnected-(GND2-Pad1)") (class "Default")
      (node (ref "GND2") (pin "1") (pinfunction "1_1") (pintype "passive"))
    )
    (net (code "78") (name "unconnected-(GND3-Pad1)") (class "Default")
      (node (ref "GND3") (pin "1") (pinfunction "1_1") (pintype "passive"))
    )
    (net (code "79") (name "unconnected-(GND4-Pad1)") (class "Default")
      (node (ref "GND4") (pin "1") (pinfunction "1_1") (pintype "passive"))
    )
    (net (code "80") (name "unconnected-(GND5-Pad1)") (class "Default")
      (node (ref "GND5") (pin "1") (pinfunction "1_1") (pintype "passive"))
    )
    (net (code "81") (name "unconnected-(J13-NC-Pad10)") (class "Default")
      (node (ref "J13") (pin "10") (pinfunction "NC_10") (pintype "passive"))
    )
    (net (code "82") (name "unconnected-(J18-NC-Pad8)") (class "Default")
      (node (ref "J18") (pin "8") (pinfunction "NC_8") (pintype "passive"))
    )
  )
)
